# 2_Power.net
KiCad netlist of a schematic drawn in Altium Designer
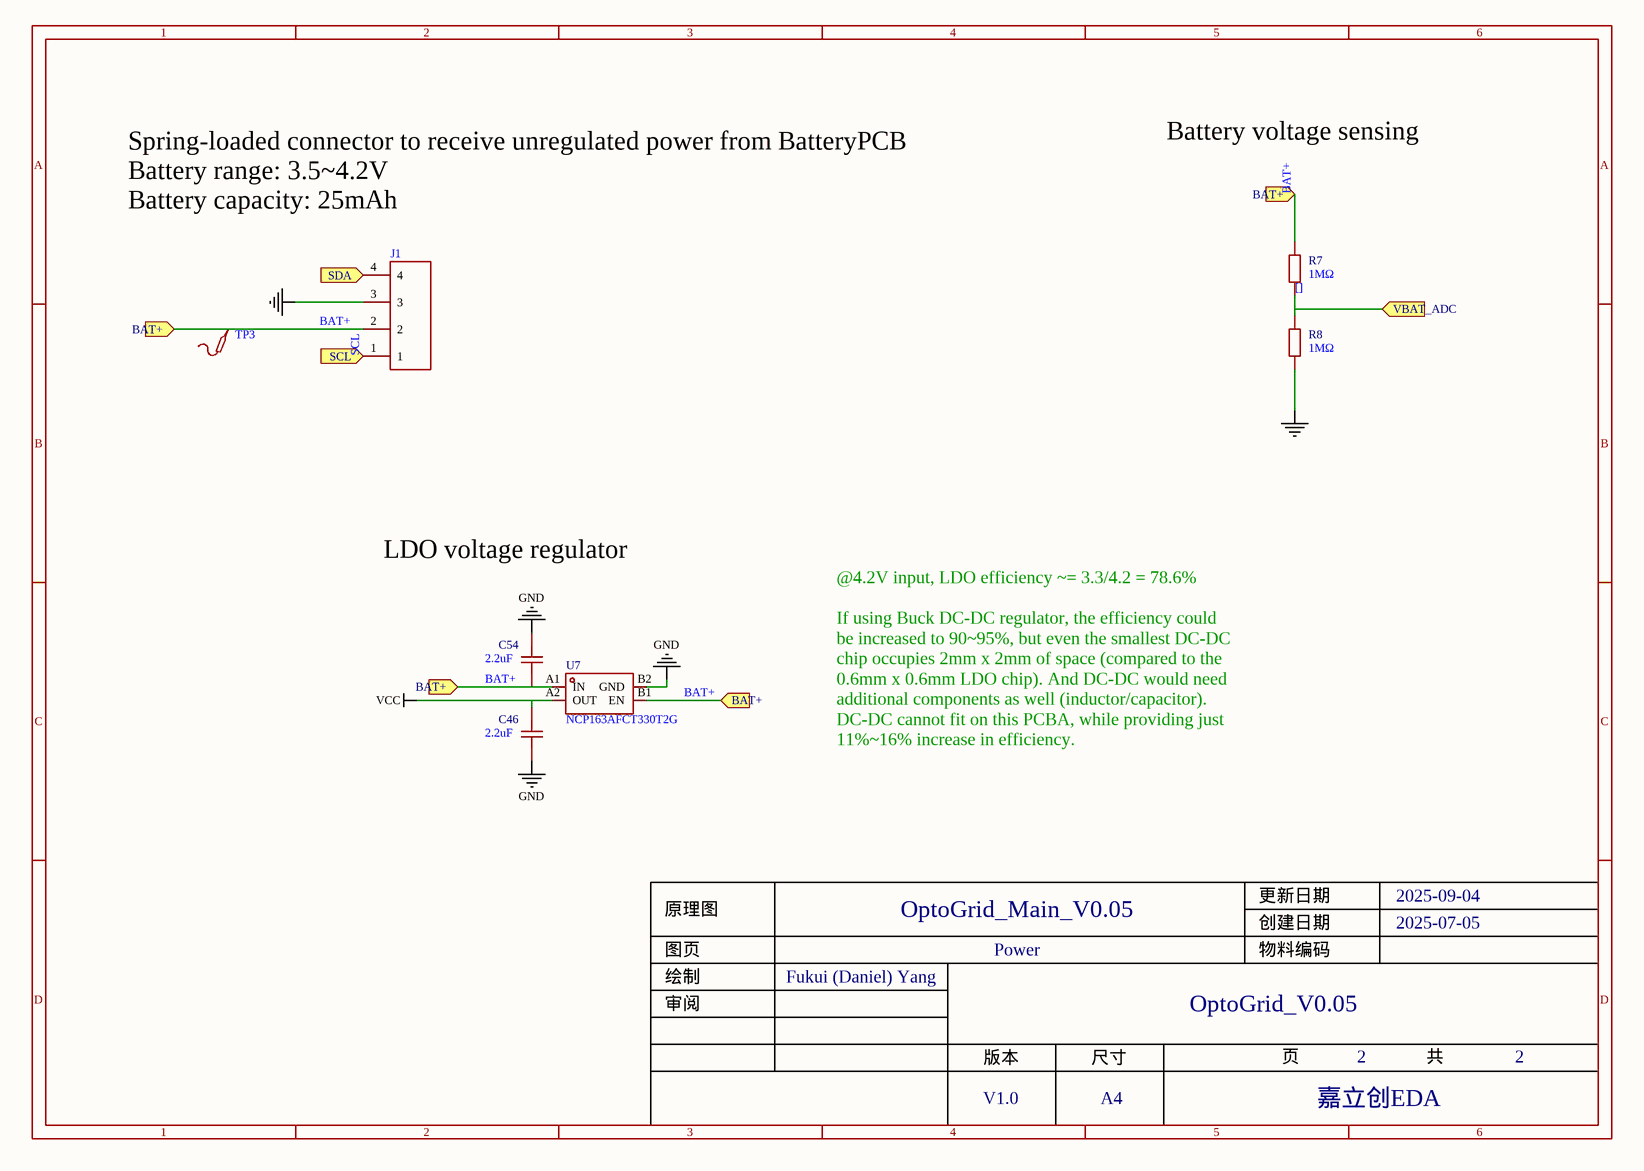
[diagram p0: 2_Power.schdoc]

(export (version "E")
  (design (tool "Eeschema 10.0.6"))
  (components
    (comp (ref "C46")
      (value "2.2uF")
      (footprint "C0201")
      (fields
        (field (name "MANUFACTURER") "muRata(村田)")
        (field (name "MANUFACTURER PART") "GRM033R61A225KE47D")
        (field (name "TOLERANCE") "±10%")
      )
      (libsource (lib "altium-import") (part "root_0_GRM033R61A225KE47D_"))
    )
    (comp (ref "C54")
      (value "2.2uF")
      (footprint "C0201")
      (fields
        (field (name "MANUFACTURER") "muRata(村田)")
        (field (name "MANUFACTURER PART") "GRM033R61A225KE47D")
        (field (name "TOLERANCE") "±10%")
      )
      (libsource (lib "altium-import") (part "root_0_GRM033R61A225KE47D_"))
    )
    (comp (ref "J1")
      (value "~")
      (footprint "811-22-004-30-002101")
      (fields
        (field (name "MANUFACTURER") "Mill-Max")
        (field (name "MANUFACTURER PART") "811-22-004-30-002101")
      )
      (libsource (lib "altium-import") (part "root_1_811-22-004-30-002101_"))
    )
    (comp (ref "R7")
      (value "1MΩ")
      (footprint "R0201")
      (fields
        (field (name "MANUFACTURER") "YAGEO(国巨)")
        (field (name "MANUFACTURER PART") "RC0201FR-071ML")
        (field (name "TOLERANCE") "±1%")
      )
      (libsource (lib "altium-import") (part "root_1_RC0201FR-071ML_"))
    )
    (comp (ref "R8")
      (value "1MΩ")
      (footprint "R0201")
      (fields
        (field (name "MANUFACTURER") "YAGEO(国巨)")
        (field (name "MANUFACTURER PART") "RC0201FR-071ML")
        (field (name "TOLERANCE") "±1%")
      )
      (libsource (lib "altium-import") (part "root_1_RC0201FR-071ML_"))
    )
    (comp (ref "TP3")
      (value "~")
      (footprint "Test-Point-0.5mm")
      (libsource (lib "altium-import") (part "root_2_Test-Point_"))
    )
    (comp (ref "U7")
      (value "NCP163AFCT330T2G")
      (footprint "WLCSP-4_L0.6-W0.6-P0.35-R2-C2-TL")
      (fields (field (name "MANUFACTURER") "onsemi(安森美)"))
      (libsource (lib "altium-import") (part "root_0_NCP163AFCT330T2G_"))
    )
  )
  (nets
    (net (code "1") (name "/BAT+") (class "Default")
      (node (ref "C54") (pin "1") (pinfunction "1_1") (pintype "passive"))
      (node (ref "J1") (pin "2") (pinfunction "2_2") (pintype "passive"))
      (node (ref "R7") (pin "2") (pinfunction "2_2") (pintype "passive"))
      (node (ref "TP3") (pin "1") (pinfunction "1_1") (pintype "passive"))
      (node (ref "U7") (pin "A1") (pinfunction "IN_A1") (pintype "passive"))
      (node (ref "U7") (pin "B1") (pinfunction "EN_B1") (pintype "passive"))
    )
    (net (code "2") (name "/SCL") (class "Default")
      (node (ref "J1") (pin "1") (pinfunction "1_1") (pintype "passive"))
    )
    (net (code "3") (name "/SDA") (class "Default")
      (node (ref "J1") (pin "4") (pinfunction "4_4") (pintype "passive"))
    )
    (net (code "4") (name "/[]") (class "Default")
      (node (ref "R7") (pin "1") (pinfunction "1_1") (pintype "passive"))
      (node (ref "R8") (pin "2") (pinfunction "2_2") (pintype "passive"))
    )
    (net (code "5") (name "GND") (class "Default")
      (node (ref "C46") (pin "1") (pinfunction "1_1") (pintype "passive"))
      (node (ref "C54") (pin "2") (pinfunction "2_2") (pintype "passive"))
      (node (ref "J1") (pin "3") (pinfunction "3_3") (pintype "passive"))
      (node (ref "R8") (pin "1") (pinfunction "1_1") (pintype "passive"))
      (node (ref "U7") (pin "B2") (pinfunction "GND_B2") (pintype "passive"))
    )
    (net (code "6") (name "VCC") (class "Default")
      (node (ref "C46") (pin "2") (pinfunction "2_2") (pintype "passive"))
      (node (ref "U7") (pin "A2") (pinfunction "OUT_A2") (pintype "passive"))
    )
  )
)
